# Fabulaser.net
KiCad netlist of a schematic drawn in EAGLE
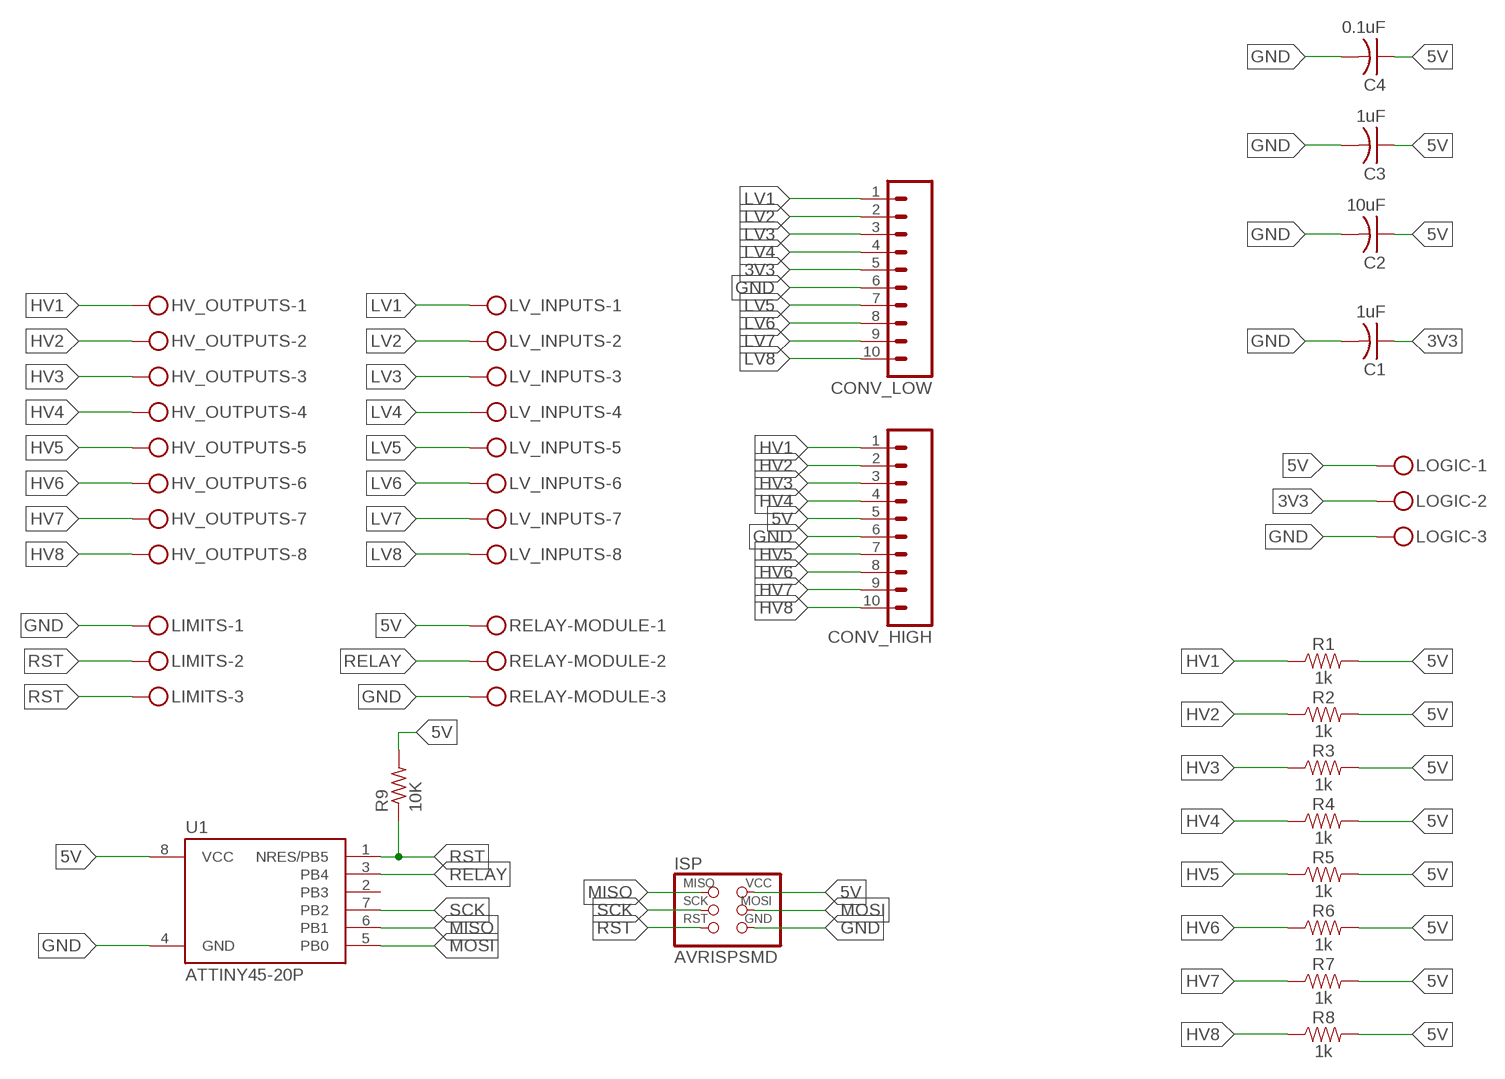
[diagram p0: schematic, sheet 1]

(export (version "E")
  (design (tool "Eeschema 10.0.6"))
  (components
    (comp (ref "C1")
      (value "1uF")
      (footprint "eagle-import:C1206FAB")
      (libsource (lib "eagle-import") (part "CAP-US1206FAB"))
    )
    (comp (ref "C2")
      (value "10uF")
      (footprint "eagle-import:C1206FAB")
      (libsource (lib "eagle-import") (part "CAP-US1206FAB"))
    )
    (comp (ref "C3")
      (value "1uF")
      (footprint "eagle-import:C1206FAB")
      (libsource (lib "eagle-import") (part "CAP-US1206FAB"))
    )
    (comp (ref "C4")
      (value "0.1uF")
      (footprint "eagle-import:C1206FAB")
      (libsource (lib "eagle-import") (part "CAP-US1206FAB"))
    )
    (comp (ref "CONV_HIGH")
      (value "M10")
      (footprint "eagle-import:10P")
      (libsource (lib "eagle-import") (part "M10"))
    )
    (comp (ref "CONV_LOW")
      (value "M10")
      (footprint "eagle-import:10P")
      (libsource (lib "eagle-import") (part "M10"))
    )
    (comp (ref "HV_OUTPUTS")
      (value "MKDSN1,5/8-5,08")
      (footprint "eagle-import:MKDSN1,5_8-5,08")
      (libsource (lib "eagle-import") (part "MKDSN1,5/8-5,08"))
    )
    (comp (ref "ISP")
      (value "AVRISPSMD")
      (footprint "eagle-import:2X03SMD")
      (fields (field (name "SPICEPREFIX") "X"))
      (libsource (lib "eagle-import") (part "AVRISPSMD"))
    )
    (comp (ref "LIMITS")
      (value "MKDSN1,5/3-5,08")
      (footprint "eagle-import:MKDSN1,5_3-5,08")
      (libsource (lib "eagle-import") (part "MKDSN1,5/3-5,08"))
    )
    (comp (ref "LOGIC")
      (value "MKDSN1,5/3-5,08")
      (footprint "eagle-import:MKDSN1,5_3-5,08")
      (libsource (lib "eagle-import") (part "MKDSN1,5/3-5,08"))
    )
    (comp (ref "LV_INPUTS")
      (value "MKDSN1,5/8-5,08")
      (footprint "eagle-import:MKDSN1,5_8-5,08")
      (libsource (lib "eagle-import") (part "MKDSN1,5/8-5,08"))
    )
    (comp (ref "R1")
      (value "1k")
      (footprint "eagle-import:AXIAL-0.3")
      (libsource (lib "eagle-import") (part "1KOHM-HORIZ-1/4W-5%"))
    )
    (comp (ref "R2")
      (value "1k")
      (footprint "eagle-import:AXIAL-0.3")
      (libsource (lib "eagle-import") (part "1KOHM-HORIZ-1/4W-5%"))
    )
    (comp (ref "R3")
      (value "1k")
      (footprint "eagle-import:AXIAL-0.3")
      (libsource (lib "eagle-import") (part "1KOHM-HORIZ-1/4W-5%"))
    )
    (comp (ref "R4")
      (value "1k")
      (footprint "eagle-import:AXIAL-0.3")
      (libsource (lib "eagle-import") (part "1KOHM-HORIZ-1/4W-5%"))
    )
    (comp (ref "R5")
      (value "1k")
      (footprint "eagle-import:AXIAL-0.3")
      (libsource (lib "eagle-import") (part "1KOHM-HORIZ-1/4W-5%"))
    )
    (comp (ref "R6")
      (value "1k")
      (footprint "eagle-import:AXIAL-0.3")
      (libsource (lib "eagle-import") (part "1KOHM-HORIZ-1/4W-5%"))
    )
    (comp (ref "R7")
      (value "1k")
      (footprint "eagle-import:AXIAL-0.3")
      (libsource (lib "eagle-import") (part "1KOHM-HORIZ-1/4W-5%"))
    )
    (comp (ref "R8")
      (value "1k")
      (footprint "eagle-import:AXIAL-0.3")
      (libsource (lib "eagle-import") (part "1KOHM-HORIZ-1/4W-1%"))
    )
    (comp (ref "R9")
      (value "10K")
      (footprint "eagle-import:R1206FAB")
      (libsource (lib "eagle-import") (part "RES-US1206FAB"))
    )
    (comp (ref "RELAY-MODULE")
      (value "MKDSN1,5/3-5,08")
      (footprint "eagle-import:MKDSN1,5_3-5,08")
      (libsource (lib "eagle-import") (part "MKDSN1,5/3-5,08"))
    )
    (comp (ref "U1")
      (value "ATTINY45-20P")
      (footprint "eagle-import:PDIP08_300MIL")
      (libsource (lib "eagle-import") (part "ATTINY45P-20"))
    )
  )
  (nets
    (net (code "1") (name "3V3") (class "Default")
      (node (ref "C1") (pin "1") (pinfunction "1_1") (pintype "passive"))
      (node (ref "CONV_LOW") (pin "5") (pinfunction "5_5") (pintype "passive"))
      (node (ref "LOGIC") (pin "2") (pinfunction "KL_2") (pintype "passive"))
    )
    (net (code "2") (name "5V") (class "Default")
      (node (ref "C2") (pin "1") (pinfunction "1_1") (pintype "passive"))
      (node (ref "C3") (pin "1") (pinfunction "1_1") (pintype "passive"))
      (node (ref "C4") (pin "1") (pinfunction "1_1") (pintype "passive"))
      (node (ref "CONV_HIGH") (pin "5") (pinfunction "5_5") (pintype "passive"))
      (node (ref "ISP") (pin "2") (pinfunction "VCC_2") (pintype "passive"))
      (node (ref "LOGIC") (pin "1") (pinfunction "KL_1") (pintype "passive"))
      (node (ref "R1") (pin "P$2") (pinfunction "2_P$2") (pintype "passive"))
      (node (ref "R2") (pin "P$2") (pinfunction "2_P$2") (pintype "passive"))
      (node (ref "R3") (pin "P$2") (pinfunction "2_P$2") (pintype "passive"))
      (node (ref "R4") (pin "P$2") (pinfunction "2_P$2") (pintype "passive"))
      (node (ref "R5") (pin "P$2") (pinfunction "2_P$2") (pintype "passive"))
      (node (ref "R6") (pin "P$2") (pinfunction "2_P$2") (pintype "passive"))
      (node (ref "R7") (pin "P$2") (pinfunction "2_P$2") (pintype "passive"))
      (node (ref "R8") (pin "P$2") (pinfunction "2_P$2") (pintype "passive"))
      (node (ref "R9") (pin "2") (pinfunction "2_2") (pintype "passive"))
      (node (ref "RELAY-MODULE") (pin "1") (pinfunction "KL_1") (pintype "passive"))
      (node (ref "U1") (pin "8") (pinfunction "VCC_8") (pintype "power_in"))
    )
    (net (code "3") (name "GND") (class "Default")
      (node (ref "C1") (pin "2") (pinfunction "2_2") (pintype "passive"))
      (node (ref "C2") (pin "2") (pinfunction "2_2") (pintype "passive"))
      (node (ref "C3") (pin "2") (pinfunction "2_2") (pintype "passive"))
      (node (ref "C4") (pin "2") (pinfunction "2_2") (pintype "passive"))
      (node (ref "CONV_HIGH") (pin "6") (pinfunction "6_6") (pintype "passive"))
      (node (ref "CONV_LOW") (pin "6") (pinfunction "6_6") (pintype "passive"))
      (node (ref "ISP") (pin "6") (pinfunction "GND_6") (pintype "passive"))
      (node (ref "LIMITS") (pin "1") (pinfunction "KL_1") (pintype "passive"))
      (node (ref "LOGIC") (pin "3") (pinfunction "KL_3") (pintype "passive"))
      (node (ref "RELAY-MODULE") (pin "3") (pinfunction "KL_3") (pintype "passive"))
      (node (ref "U1") (pin "4") (pinfunction "GND_4") (pintype "power_in"))
    )
    (net (code "4") (name "HV1") (class "Default")
      (node (ref "CONV_HIGH") (pin "1") (pinfunction "1_1") (pintype "passive"))
      (node (ref "HV_OUTPUTS") (pin "1") (pinfunction "KL_1") (pintype "passive"))
      (node (ref "R1") (pin "P$1") (pinfunction "1_P$1") (pintype "passive"))
    )
    (net (code "5") (name "HV2") (class "Default")
      (node (ref "CONV_HIGH") (pin "2") (pinfunction "2_2") (pintype "passive"))
      (node (ref "HV_OUTPUTS") (pin "2") (pinfunction "KL_2") (pintype "passive"))
      (node (ref "R2") (pin "P$1") (pinfunction "1_P$1") (pintype "passive"))
    )
    (net (code "6") (name "HV3") (class "Default")
      (node (ref "CONV_HIGH") (pin "3") (pinfunction "3_3") (pintype "passive"))
      (node (ref "HV_OUTPUTS") (pin "3") (pinfunction "KL_3") (pintype "passive"))
      (node (ref "R3") (pin "P$1") (pinfunction "1_P$1") (pintype "passive"))
    )
    (net (code "7") (name "HV4") (class "Default")
      (node (ref "CONV_HIGH") (pin "4") (pinfunction "4_4") (pintype "passive"))
      (node (ref "HV_OUTPUTS") (pin "4") (pinfunction "KL_4") (pintype "passive"))
      (node (ref "R4") (pin "P$1") (pinfunction "1_P$1") (pintype "passive"))
    )
    (net (code "8") (name "HV5") (class "Default")
      (node (ref "CONV_HIGH") (pin "7") (pinfunction "7_7") (pintype "passive"))
      (node (ref "HV_OUTPUTS") (pin "5") (pinfunction "KL_5") (pintype "passive"))
      (node (ref "R5") (pin "P$1") (pinfunction "1_P$1") (pintype "passive"))
    )
    (net (code "9") (name "HV6") (class "Default")
      (node (ref "CONV_HIGH") (pin "8") (pinfunction "8_8") (pintype "passive"))
      (node (ref "HV_OUTPUTS") (pin "6") (pinfunction "KL_6") (pintype "passive"))
      (node (ref "R6") (pin "P$1") (pinfunction "1_P$1") (pintype "passive"))
    )
    (net (code "10") (name "HV7") (class "Default")
      (node (ref "CONV_HIGH") (pin "9") (pinfunction "9_9") (pintype "passive"))
      (node (ref "HV_OUTPUTS") (pin "7") (pinfunction "KL_7") (pintype "passive"))
      (node (ref "R7") (pin "P$1") (pinfunction "1_P$1") (pintype "passive"))
    )
    (net (code "11") (name "HV8") (class "Default")
      (node (ref "CONV_HIGH") (pin "10") (pinfunction "10_10") (pintype "passive"))
      (node (ref "HV_OUTPUTS") (pin "8") (pinfunction "KL_8") (pintype "passive"))
      (node (ref "R8") (pin "P$1") (pinfunction "1_P$1") (pintype "passive"))
    )
    (net (code "12") (name "LV1") (class "Default")
      (node (ref "CONV_LOW") (pin "1") (pinfunction "1_1") (pintype "passive"))
      (node (ref "LV_INPUTS") (pin "1") (pinfunction "KL_1") (pintype "passive"))
    )
    (net (code "13") (name "LV2") (class "Default")
      (node (ref "CONV_LOW") (pin "2") (pinfunction "2_2") (pintype "passive"))
      (node (ref "LV_INPUTS") (pin "2") (pinfunction "KL_2") (pintype "passive"))
    )
    (net (code "14") (name "LV3") (class "Default")
      (node (ref "CONV_LOW") (pin "3") (pinfunction "3_3") (pintype "passive"))
      (node (ref "LV_INPUTS") (pin "3") (pinfunction "KL_3") (pintype "passive"))
    )
    (net (code "15") (name "LV4") (class "Default")
      (node (ref "CONV_LOW") (pin "4") (pinfunction "4_4") (pintype "passive"))
      (node (ref "LV_INPUTS") (pin "4") (pinfunction "KL_4") (pintype "passive"))
    )
    (net (code "16") (name "LV5") (class "Default")
      (node (ref "CONV_LOW") (pin "7") (pinfunction "7_7") (pintype "passive"))
      (node (ref "LV_INPUTS") (pin "5") (pinfunction "KL_5") (pintype "passive"))
    )
    (net (code "17") (name "LV6") (class "Default")
      (node (ref "CONV_LOW") (pin "8") (pinfunction "8_8") (pintype "passive"))
      (node (ref "LV_INPUTS") (pin "6") (pinfunction "KL_6") (pintype "passive"))
    )
    (net (code "18") (name "LV7") (class "Default")
      (node (ref "CONV_LOW") (pin "9") (pinfunction "9_9") (pintype "passive"))
      (node (ref "LV_INPUTS") (pin "7") (pinfunction "KL_7") (pintype "passive"))
    )
    (net (code "19") (name "LV8") (class "Default")
      (node (ref "CONV_LOW") (pin "10") (pinfunction "10_10") (pintype "passive"))
      (node (ref "LV_INPUTS") (pin "8") (pinfunction "KL_8") (pintype "passive"))
    )
    (net (code "20") (name "MISO") (class "Default")
      (node (ref "ISP") (pin "1") (pinfunction "MISO_1") (pintype "passive"))
      (node (ref "U1") (pin "6") (pinfunction "PB1_6") (pintype "bidirectional"))
    )
    (net (code "21") (name "MOSI") (class "Default")
      (node (ref "ISP") (pin "4") (pinfunction "MOSI_4") (pintype "passive"))
      (node (ref "U1") (pin "5") (pinfunction "PB0_5") (pintype "bidirectional"))
    )
    (net (code "22") (name "RELAY") (class "Default")
      (node (ref "RELAY-MODULE") (pin "2") (pinfunction "KL_2") (pintype "passive"))
      (node (ref "U1") (pin "3") (pinfunction "PB4_3") (pintype "bidirectional"))
    )
    (net (code "23") (name "RST") (class "Default")
      (node (ref "ISP") (pin "5") (pinfunction "RST_5") (pintype "passive"))
      (node (ref "LIMITS") (pin "2") (pinfunction "KL_2") (pintype "passive"))
      (node (ref "LIMITS") (pin "3") (pinfunction "KL_3") (pintype "passive"))
      (node (ref "R9") (pin "1") (pinfunction "1_1") (pintype "passive"))
      (node (ref "U1") (pin "1") (pinfunction "NRES/PB5_1") (pintype "bidirectional"))
    )
    (net (code "24") (name "SCK") (class "Default")
      (node (ref "ISP") (pin "3") (pinfunction "SCK_3") (pintype "passive"))
      (node (ref "U1") (pin "7") (pinfunction "PB2_7") (pintype "bidirectional"))
    )
    (net (code "25") (name "unconnected-(U1-PB3-Pad2)") (class "Default")
      (node (ref "U1") (pin "2") (pinfunction "PB3_2") (pintype "bidirectional"))
    )
  )
)
